# assign2.net
KiCad netlist of a schematic drawn in EAGLE
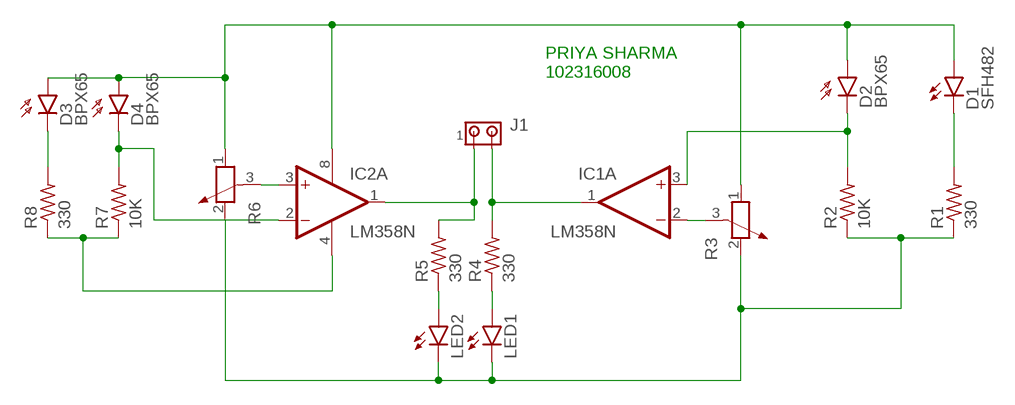
[diagram p0: schematic, sheet 1]

(export (version "E")
  (design (tool "Eeschema 10.0.6"))
  (components
    (comp (ref "D1")
      (value "SFH482")
      (footprint "eagle-import:SFH482")
      (libsource (lib "eagle-import") (part "SFH482"))
    )
    (comp (ref "D2")
      (value "BPX65")
      (footprint "eagle-import:BPX65")
      (fields (field (name "MPN") "BPX65."))
      (libsource (lib "eagle-import") (part "BPX65"))
    )
    (comp (ref "D3")
      (value "BPX65")
      (footprint "eagle-import:BPX65")
      (fields (field (name "MPN") "BPX65."))
      (libsource (lib "eagle-import") (part "BPX65"))
    )
    (comp (ref "D4")
      (value "BPX65")
      (footprint "eagle-import:BPX65")
      (fields (field (name "MPN") "BPX65."))
      (libsource (lib "eagle-import") (part "BPX65"))
    )
    (comp (ref "IC1")
      (value "LM358N")
      (footprint "eagle-import:DIL08")
      (libsource (lib "eagle-import") (part "LM358N"))
    )
    (comp (ref "IC2")
      (value "LM358N")
      (footprint "eagle-import:DIL08")
      (libsource (lib "eagle-import") (part "LM358N"))
    )
    (comp (ref "J1")
      (value "MTA02-100")
      (footprint "eagle-import:10X02MTA")
      (libsource (lib "eagle-import") (part "MTA02-100"))
    )
    (comp (ref "LED1")
      (value "LED3MM")
      (footprint "eagle-import:LED3MM")
      (libsource (lib "eagle-import") (part "LED3MM"))
    )
    (comp (ref "LED2")
      (value "LED3MM")
      (footprint "eagle-import:LED3MM")
      (libsource (lib "eagle-import") (part "LED3MM"))
    )
    (comp (ref "R1")
      (value "330")
      (footprint "eagle-import:0204_5")
      (libsource (lib "eagle-import") (part "R-US_0204/5"))
    )
    (comp (ref "R2")
      (value "10K")
      (footprint "eagle-import:0204_5")
      (libsource (lib "eagle-import") (part "R-US_0204/5"))
    )
    (comp (ref "R3")
      (value "POTENTIOMETER_PT-10")
      (footprint "eagle-import:PT-10")
      (libsource (lib "eagle-import") (part "POTENTIOMETER_PT-10"))
    )
    (comp (ref "R4")
      (value "330")
      (footprint "eagle-import:0204_5")
      (libsource (lib "eagle-import") (part "R-US_0204/5"))
    )
    (comp (ref "R5")
      (value "330")
      (footprint "eagle-import:0204_5")
      (libsource (lib "eagle-import") (part "R-US_0204/5"))
    )
    (comp (ref "R6")
      (value "POTENTIOMETER_PT-10")
      (footprint "eagle-import:PT-10")
      (libsource (lib "eagle-import") (part "POTENTIOMETER_PT-10"))
    )
    (comp (ref "R7")
      (value "10K")
      (footprint "eagle-import:0204_5")
      (libsource (lib "eagle-import") (part "R-US_0204/5"))
    )
    (comp (ref "R8")
      (value "330")
      (footprint "eagle-import:0204_5")
      (libsource (lib "eagle-import") (part "R-US_0204/5"))
    )
  )
  (nets
    (net (code "1") (name "Net-(D1-C)") (class "Default")
      (node (ref "D1") (pin "K") (pinfunction "C_K") (pintype "passive"))
      (node (ref "R1") (pin "2") (pinfunction "2_2") (pintype "passive"))
    )
    (net (code "2") (name "Net-(D2-C)") (class "Default")
      (node (ref "D2") (pin "K") (pinfunction "C_K") (pintype "passive"))
      (node (ref "IC1") (pin "3") (pinfunction "+IN_3") (pintype "input"))
      (node (ref "R2") (pin "2") (pinfunction "2_2") (pintype "passive"))
    )
    (net (code "3") (name "Net-(D3-C)") (class "Default")
      (node (ref "D3") (pin "K") (pinfunction "C_K") (pintype "passive"))
      (node (ref "R8") (pin "2") (pinfunction "2_2") (pintype "passive"))
    )
    (net (code "4") (name "Net-(D4-C)") (class "Default")
      (node (ref "D4") (pin "K") (pinfunction "C_K") (pintype "passive"))
      (node (ref "IC2") (pin "2") (pinfunction "-IN_2") (pintype "input"))
      (node (ref "R7") (pin "2") (pinfunction "2_2") (pintype "passive"))
    )
    (net (code "5") (name "Net-(IC1A--IN)") (class "Default")
      (node (ref "IC1") (pin "2") (pinfunction "-IN_2") (pintype "input"))
      (node (ref "R3") (pin "3") (pinfunction "3_3") (pintype "passive"))
    )
    (net (code "6") (name "Net-(IC1A-OUT)") (class "Default")
      (node (ref "IC1") (pin "1") (pinfunction "OUT_1") (pintype "output"))
      (node (ref "J1") (pin "2") (pinfunction "2_2") (pintype "passive"))
      (node (ref "R4") (pin "2") (pinfunction "2_2") (pintype "passive"))
    )
    (net (code "7") (name "Net-(IC2A-+IN)") (class "Default")
      (node (ref "IC2") (pin "3") (pinfunction "+IN_3") (pintype "input"))
      (node (ref "R6") (pin "3") (pinfunction "3_3") (pintype "passive"))
    )
    (net (code "8") (name "Net-(IC2A-OUT)") (class "Default")
      (node (ref "IC2") (pin "1") (pinfunction "OUT_1") (pintype "output"))
      (node (ref "J1") (pin "1") (pinfunction "1_1") (pintype "passive"))
      (node (ref "R5") (pin "2") (pinfunction "2_2") (pintype "passive"))
    )
    (net (code "9") (name "Net-(IC2C-V+)") (class "Default")
      (node (ref "D1") (pin "A") (pinfunction "A_A") (pintype "passive"))
      (node (ref "D2") (pin "A") (pinfunction "A_A") (pintype "passive"))
      (node (ref "D3") (pin "A") (pinfunction "A_A") (pintype "passive"))
      (node (ref "D4") (pin "A") (pinfunction "A_A") (pintype "passive"))
      (node (ref "IC2") (pin "8") (pinfunction "V+_8") (pintype "power_in"))
      (node (ref "R3") (pin "1") (pinfunction "1_1") (pintype "passive"))
      (node (ref "R6") (pin "1") (pinfunction "1_1") (pintype "passive"))
    )
    (net (code "10") (name "Net-(IC2C-V-)") (class "Default")
      (node (ref "IC2") (pin "4") (pinfunction "V-_4") (pintype "power_in"))
      (node (ref "R7") (pin "1") (pinfunction "1_1") (pintype "passive"))
      (node (ref "R8") (pin "1") (pinfunction "1_1") (pintype "passive"))
    )
    (net (code "11") (name "Net-(LED1-C)") (class "Default")
      (node (ref "LED1") (pin "K") (pinfunction "C_K") (pintype "passive"))
      (node (ref "LED2") (pin "K") (pinfunction "C_K") (pintype "passive"))
      (node (ref "R1") (pin "1") (pinfunction "1_1") (pintype "passive"))
      (node (ref "R2") (pin "1") (pinfunction "1_1") (pintype "passive"))
      (node (ref "R3") (pin "2") (pinfunction "2_2") (pintype "passive"))
      (node (ref "R6") (pin "2") (pinfunction "2_2") (pintype "passive"))
    )
    (net (code "12") (name "Net-(LED1-PadA)") (class "Default")
      (node (ref "LED1") (pin "A") (pinfunction "A_A") (pintype "passive"))
      (node (ref "R4") (pin "1") (pinfunction "1_1") (pintype "passive"))
    )
    (net (code "13") (name "Net-(LED2-PadA)") (class "Default")
      (node (ref "LED2") (pin "A") (pinfunction "A_A") (pintype "passive"))
      (node (ref "R5") (pin "1") (pinfunction "1_1") (pintype "passive"))
    )
  )
)
